# ir-sensor-breakout-mk-2_3-pth.net
KiCad netlist of a schematic drawn in EAGLE
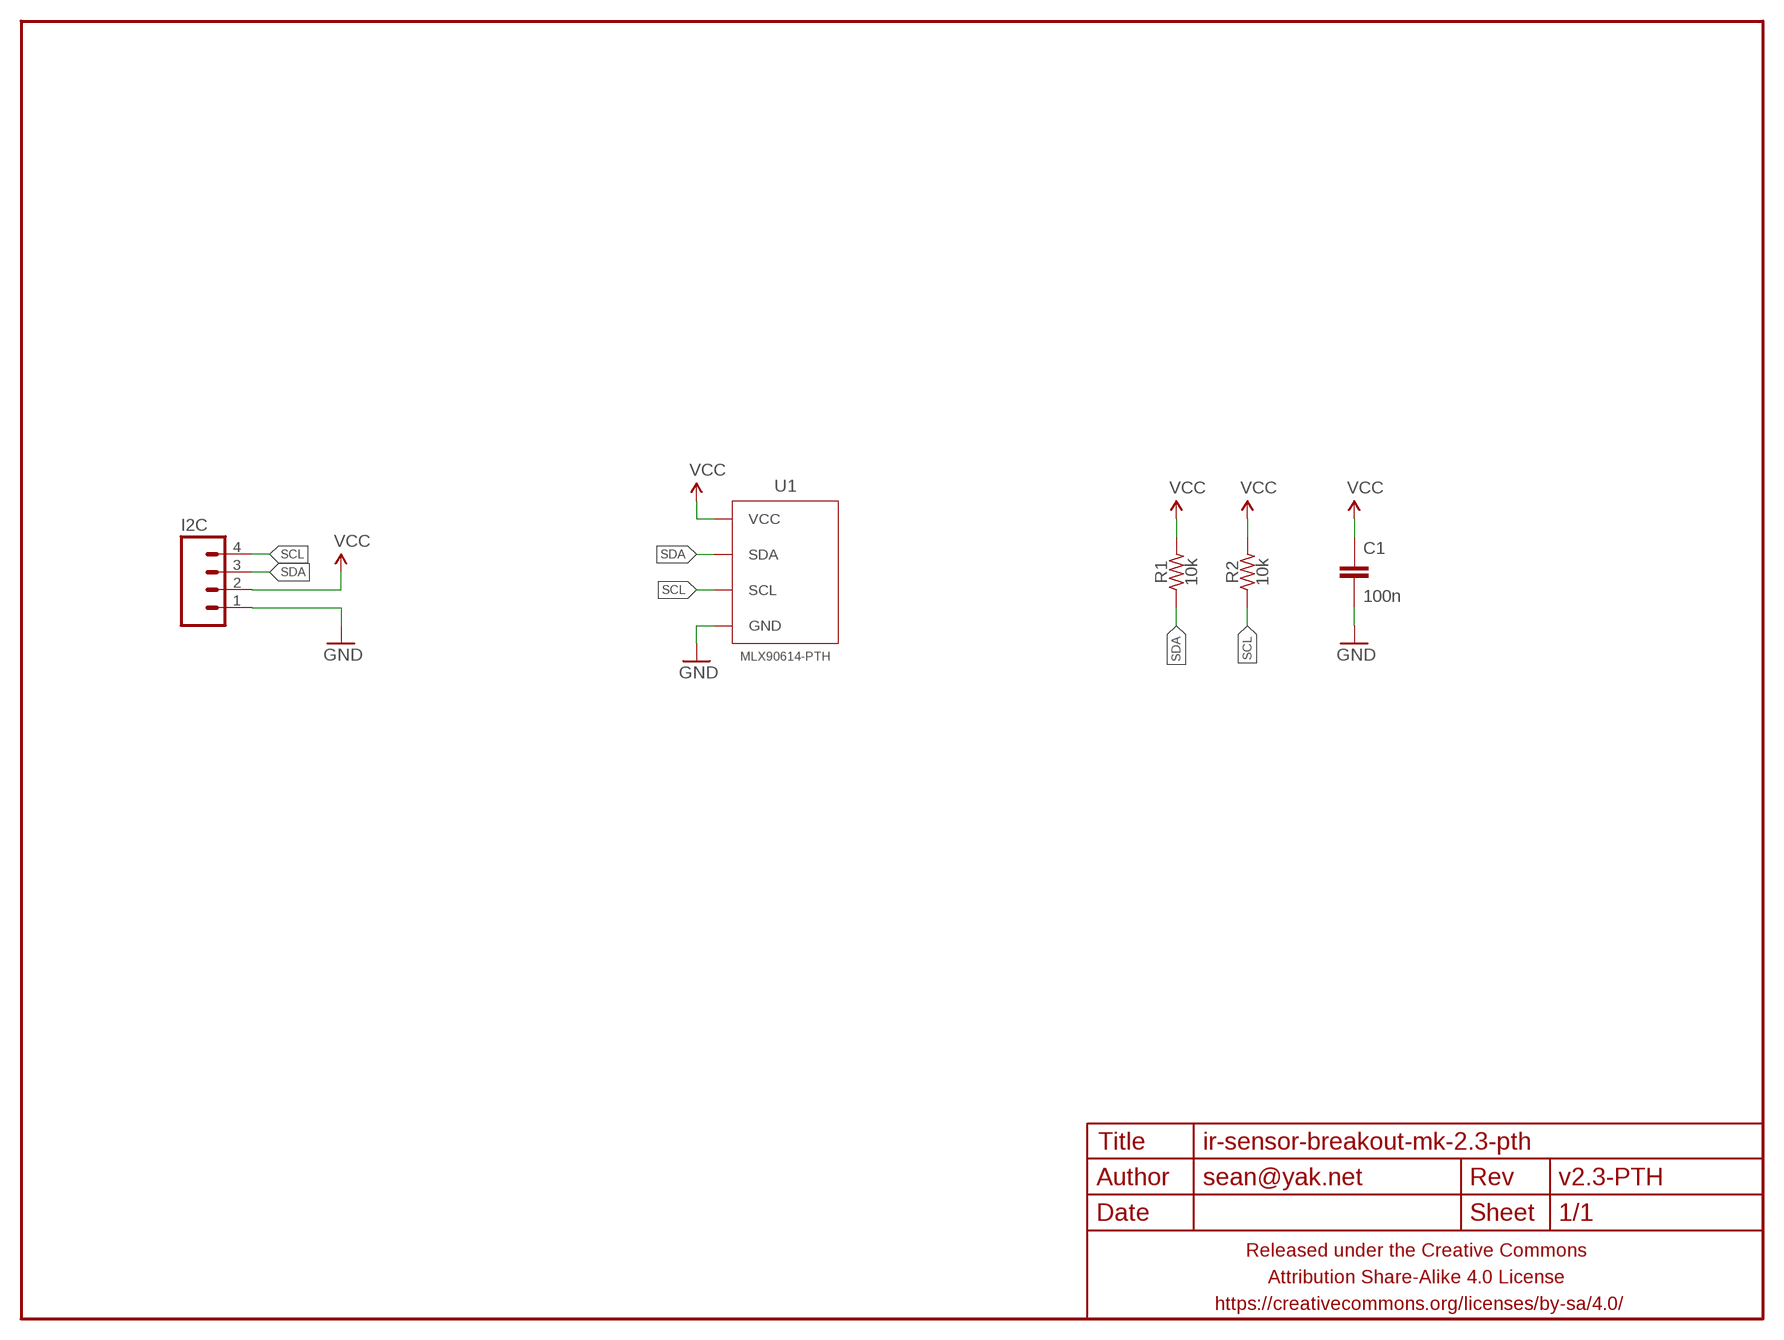
[diagram p0: schematic, sheet 1]

(export (version "E")
  (design (tool "Eeschema 10.0.6"))
  (components
    (comp (ref "C1")
      (value "100n")
      (footprint "eagle-import:C025-024X044")
      (libsource (lib "eagle-import") (part "CAPACITOR-CERAMIC025-024X044"))
    )
    (comp (ref "FRAME1")
      (value "FRAME-LETTERNO_PACKAGE")
      (footprint "eagle-import:DUMMY")
      (fields (field (name "DESIGNER") "sean@yak.net") (field (name "VERSION") "v2.3-PTH"))
      (libsource (lib "eagle-import") (part "FRAME-LETTERNO_PACKAGE"))
    )
    (comp (ref "I2C")
      (value "M04JST-PTH-VERT")
      (footprint "eagle-import:JST-4-PH-VERT-PTH")
      (libsource (lib "eagle-import") (part "M04JST-PTH-VERT"))
    )
    (comp (ref "R1")
      (value "10k")
      (footprint "eagle-import:RESISTOR-AXIAL-PTH-5.08MM")
      (libsource (lib "eagle-import") (part "RESISTORPTH-AXIAL-5.08MM"))
    )
    (comp (ref "R2")
      (value "10k")
      (footprint "eagle-import:RESISTOR-AXIAL-PTH-5.08MM")
      (libsource (lib "eagle-import") (part "RESISTORPTH-AXIAL-5.08MM"))
    )
    (comp (ref "U1")
      (value "MLX90614-PTH")
      (footprint "eagle-import:TO-39-4")
      (libsource (lib "eagle-import") (part "MLX906145V-PTH"))
    )
  )
  (nets
    (net (code "1") (name "GND") (class "Default")
      (node (ref "C1") (pin "2") (pinfunction "2_2") (pintype "passive"))
      (node (ref "I2C") (pin "1") (pinfunction "1_1") (pintype "passive"))
      (node (ref "U1") (pin "4") (pinfunction "GND_4") (pintype "bidirectional"))
    )
    (net (code "2") (name "SCL") (class "Default")
      (node (ref "I2C") (pin "4") (pinfunction "4_4") (pintype "passive"))
      (node (ref "R2") (pin "P$1") (pinfunction "1_P$1") (pintype "passive"))
      (node (ref "U1") (pin "1") (pinfunction "SCL_1") (pintype "bidirectional"))
    )
    (net (code "3") (name "SDA") (class "Default")
      (node (ref "I2C") (pin "3") (pinfunction "3_3") (pintype "passive"))
      (node (ref "R1") (pin "P$1") (pinfunction "1_P$1") (pintype "passive"))
      (node (ref "U1") (pin "2") (pinfunction "SDA_2") (pintype "bidirectional"))
    )
    (net (code "4") (name "VCC") (class "Default")
      (node (ref "C1") (pin "1") (pinfunction "1_1") (pintype "passive"))
      (node (ref "I2C") (pin "2") (pinfunction "2_2") (pintype "passive"))
      (node (ref "R1") (pin "P$2") (pinfunction "2_P$2") (pintype "passive"))
      (node (ref "R2") (pin "P$2") (pinfunction "2_P$2") (pintype "passive"))
      (node (ref "U1") (pin "3") (pinfunction "VCC_3") (pintype "bidirectional"))
    )
  )
)
